# LPCB280_-_DRIVERS.net
KiCad netlist of a schematic drawn in Altium Designer
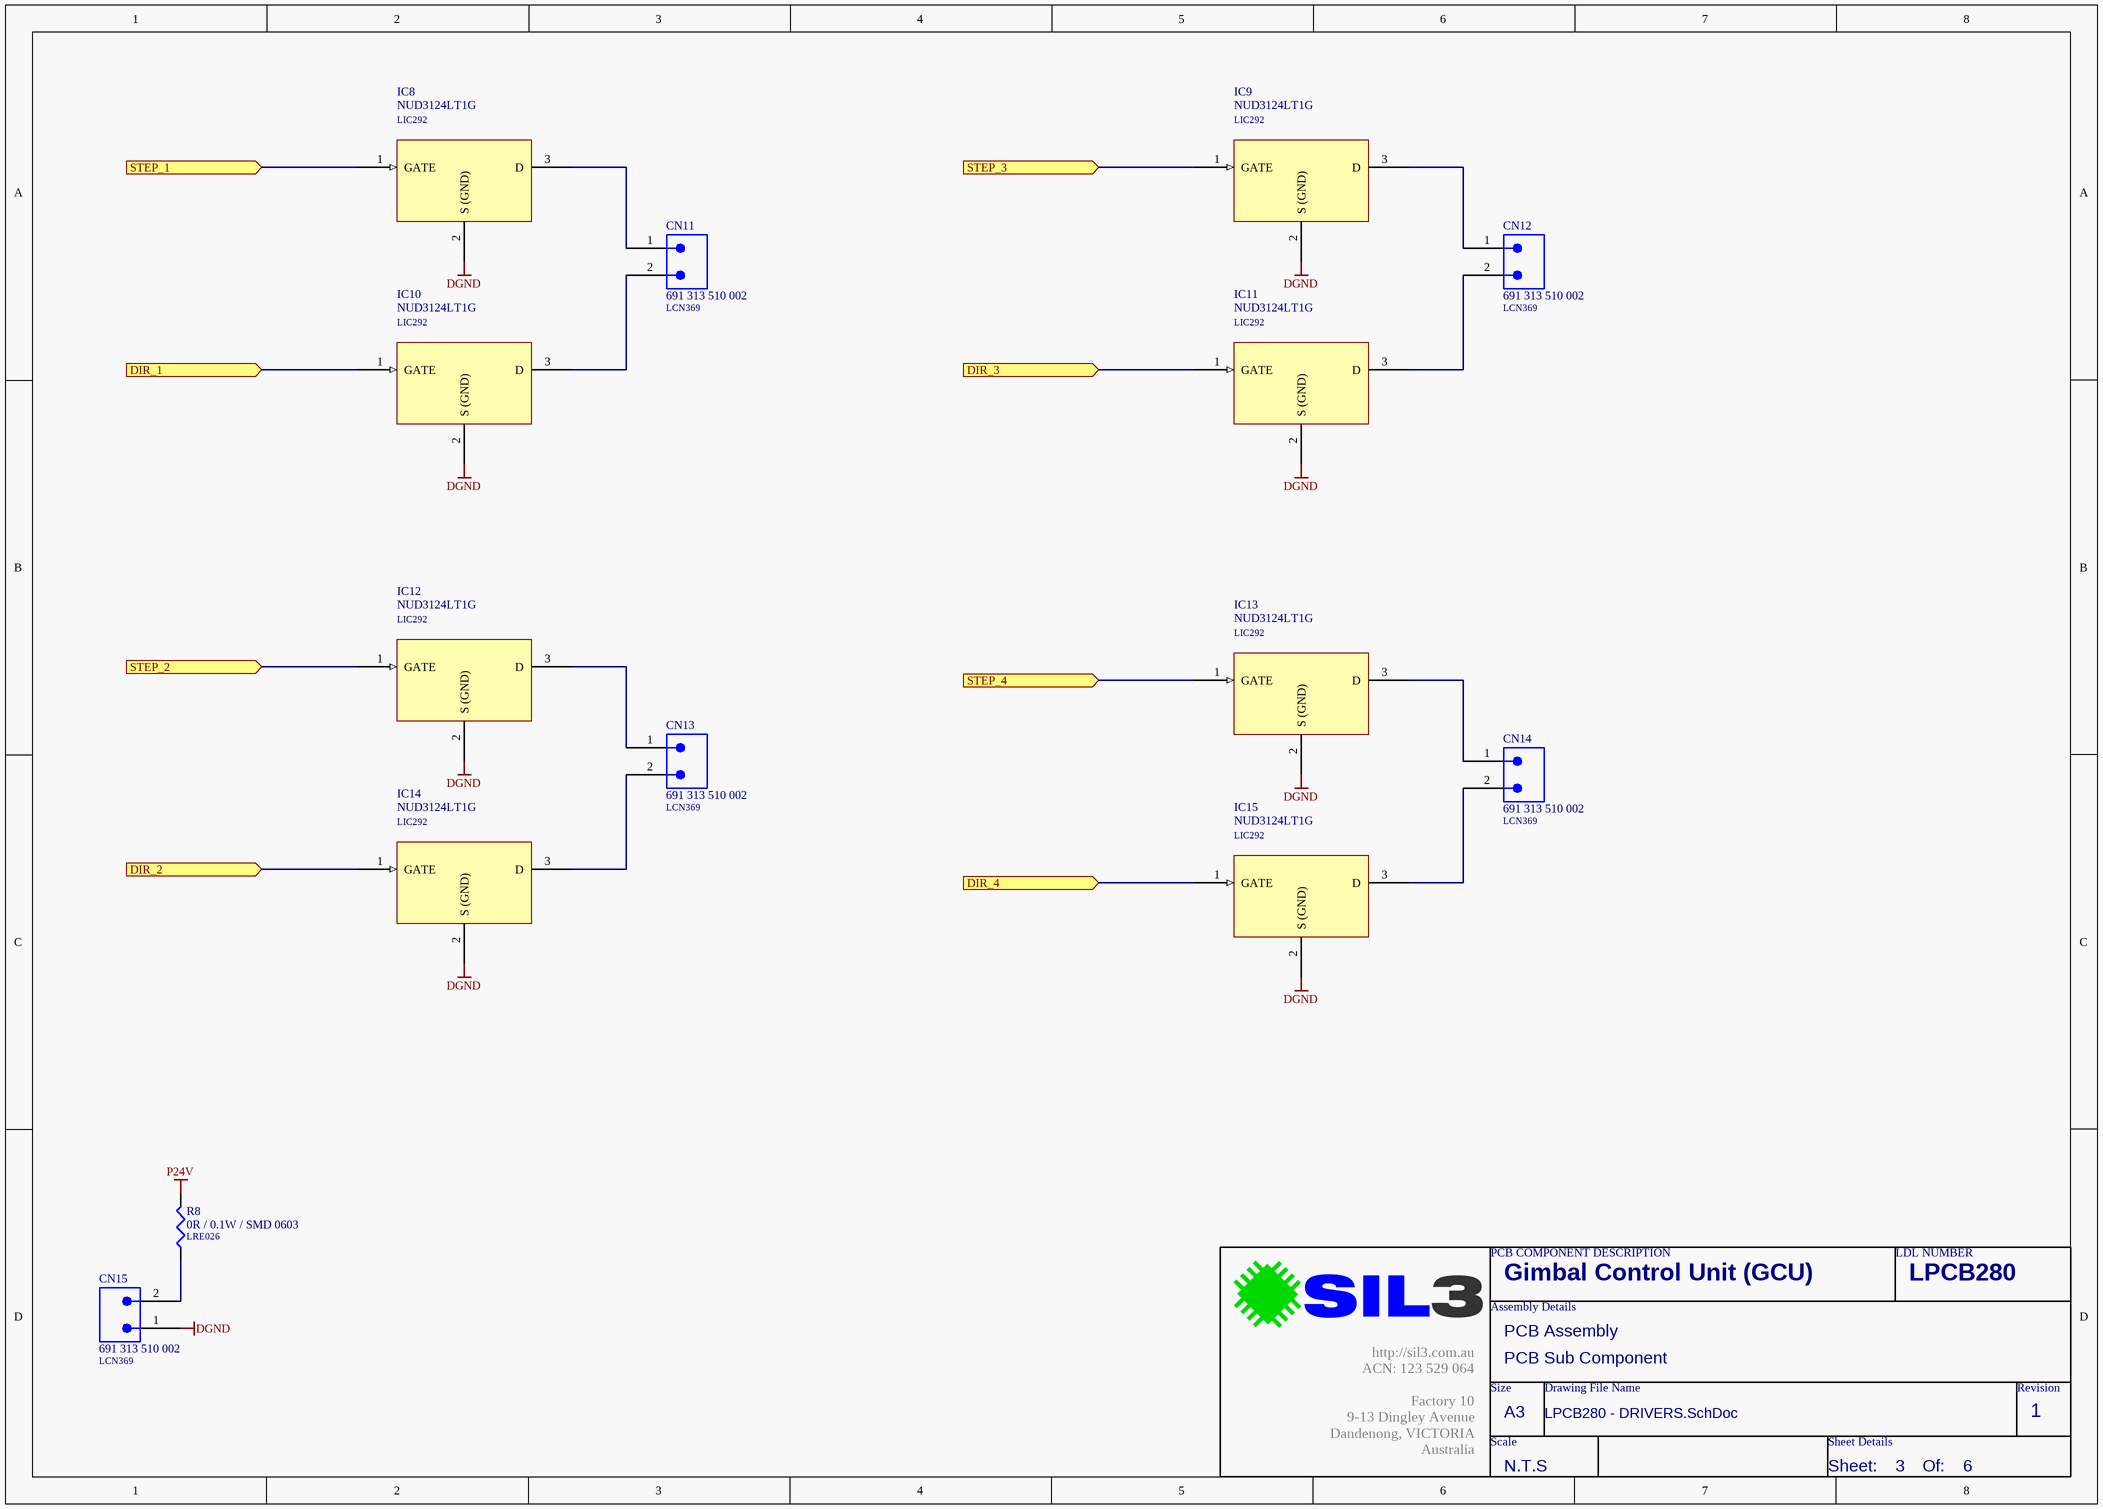
[diagram p0: LPCB280 - DRIVERS.SchDoc]

(export (version "E")
  (design (tool "Eeschema 10.0.6"))
  (components
    (comp (ref "CN11")
      (value "691 313 510 002")
      (footprint "691 313 510 002")
      (description "Connector, Pluggable Terminal Block, 5.08mm, 2 Way, PTH")
      (fields (field (name "LDL_NUMBER") "LCN369"))
      (libsource (lib "LDL_Connectors") (part "691 313 510 002"))
    )
    (comp (ref "CN12")
      (value "691 313 510 002")
      (footprint "691 313 510 002")
      (description "Connector, Pluggable Terminal Block, 5.08mm, 2 Way, PTH")
      (fields (field (name "LDL_NUMBER") "LCN369"))
      (libsource (lib "LDL_Connectors") (part "691 313 510 002"))
    )
    (comp (ref "CN13")
      (value "691 313 510 002")
      (footprint "691 313 510 002")
      (description "Connector, Pluggable Terminal Block, 5.08mm, 2 Way, PTH")
      (fields (field (name "LDL_NUMBER") "LCN369"))
      (libsource (lib "LDL_Connectors") (part "691 313 510 002"))
    )
    (comp (ref "CN14")
      (value "691 313 510 002")
      (footprint "691 313 510 002")
      (description "Connector, Pluggable Terminal Block, 5.08mm, 2 Way, PTH")
      (fields (field (name "LDL_NUMBER") "LCN369"))
      (libsource (lib "LDL_Connectors") (part "691 313 510 002"))
    )
    (comp (ref "CN15")
      (value "691 313 510 002")
      (footprint "691 313 510 002")
      (description "Connector, Pluggable Terminal Block, 5.08mm, 2 Way, PTH")
      (fields (field (name "LDL_NUMBER") "LCN369"))
      (libsource (lib "LDL_Connectors") (part "691 313 510 002"))
    )
    (comp (ref "IC8")
      (value "NUD3124LT1G")
      (footprint "LFP021__SOT23")
      (description "IC, Relay Driver, 28V Industrial, SMD SOT23 [LIC292]")
      (fields (field (name "LDL_NUMBER") "LIC292"))
      (libsource (lib "LDL_Semiconductors") (part "NUD3124LT1G"))
    )
    (comp (ref "IC9")
      (value "NUD3124LT1G")
      (footprint "LFP021__SOT23")
      (description "IC, Relay Driver, 28V Industrial, SMD SOT23 [LIC292]")
      (fields (field (name "LDL_NUMBER") "LIC292"))
      (libsource (lib "LDL_Semiconductors") (part "NUD3124LT1G"))
    )
    (comp (ref "IC10")
      (value "NUD3124LT1G")
      (footprint "LFP021__SOT23")
      (description "IC, Relay Driver, 28V Industrial, SMD SOT23 [LIC292]")
      (fields (field (name "LDL_NUMBER") "LIC292"))
      (libsource (lib "LDL_Semiconductors") (part "NUD3124LT1G"))
    )
    (comp (ref "IC11")
      (value "NUD3124LT1G")
      (footprint "LFP021__SOT23")
      (description "IC, Relay Driver, 28V Industrial, SMD SOT23 [LIC292]")
      (fields (field (name "LDL_NUMBER") "LIC292"))
      (libsource (lib "LDL_Semiconductors") (part "NUD3124LT1G"))
    )
    (comp (ref "IC12")
      (value "NUD3124LT1G")
      (footprint "LFP021__SOT23")
      (description "IC, Relay Driver, 28V Industrial, SMD SOT23 [LIC292]")
      (fields (field (name "LDL_NUMBER") "LIC292"))
      (libsource (lib "LDL_Semiconductors") (part "NUD3124LT1G"))
    )
    (comp (ref "IC13")
      (value "NUD3124LT1G")
      (footprint "LFP021__SOT23")
      (description "IC, Relay Driver, 28V Industrial, SMD SOT23 [LIC292]")
      (fields (field (name "LDL_NUMBER") "LIC292"))
      (libsource (lib "LDL_Semiconductors") (part "NUD3124LT1G"))
    )
    (comp (ref "IC14")
      (value "NUD3124LT1G")
      (footprint "LFP021__SOT23")
      (description "IC, Relay Driver, 28V Industrial, SMD SOT23 [LIC292]")
      (fields (field (name "LDL_NUMBER") "LIC292"))
      (libsource (lib "LDL_Semiconductors") (part "NUD3124LT1G"))
    )
    (comp (ref "IC15")
      (value "NUD3124LT1G")
      (footprint "LFP021__SOT23")
      (description "IC, Relay Driver, 28V Industrial, SMD SOT23 [LIC292]")
      (fields (field (name "LDL_NUMBER") "LIC292"))
      (libsource (lib "LDL_Semiconductors") (part "NUD3124LT1G"))
    )
    (comp (ref "R8")
      (value "0R / 0.1W / SMD 0603")
      (footprint "LFP020__CR1608-0603-IPC7351_B")
      (description "Resistor, Ceramic Chip, 0R, 0.1W, SMD 0603 [LRE026]")
      (fields (field (name "LDL_NUMBER") "LRE026"))
      (libsource (lib "LDL_Resistors") (part "0R / 0.1W / SMD 0603"))
    )
  )
  (nets
    (net (code "1") (name "/DIR_1") (class "Default")
      (node (ref "IC10") (pin "1") (pinfunction "GATE_1") (pintype "input"))
    )
    (net (code "2") (name "/DIR_2") (class "Default")
      (node (ref "IC14") (pin "1") (pinfunction "GATE_1") (pintype "input"))
    )
    (net (code "3") (name "/DIR_3") (class "Default")
      (node (ref "IC11") (pin "1") (pinfunction "GATE_1") (pintype "input"))
    )
    (net (code "4") (name "/DIR_4") (class "Default")
      (node (ref "IC15") (pin "1") (pinfunction "GATE_1") (pintype "input"))
    )
    (net (code "5") (name "/STEP_1") (class "Default")
      (node (ref "IC8") (pin "1") (pinfunction "GATE_1") (pintype "input"))
    )
    (net (code "6") (name "/STEP_2") (class "Default")
      (node (ref "IC12") (pin "1") (pinfunction "GATE_1") (pintype "input"))
    )
    (net (code "7") (name "/STEP_3") (class "Default")
      (node (ref "IC9") (pin "1") (pinfunction "GATE_1") (pintype "input"))
    )
    (net (code "8") (name "/STEP_4") (class "Default")
      (node (ref "IC13") (pin "1") (pinfunction "GATE_1") (pintype "input"))
    )
    (net (code "9") (name "DGND") (class "Default")
      (node (ref "CN15") (pin "1") (pinfunction "1_1") (pintype "passive"))
      (node (ref "IC10") (pin "2") (pinfunction "S_(GND)_2") (pintype "passive"))
      (node (ref "IC11") (pin "2") (pinfunction "S_(GND)_2") (pintype "passive"))
      (node (ref "IC12") (pin "2") (pinfunction "S_(GND)_2") (pintype "passive"))
      (node (ref "IC13") (pin "2") (pinfunction "S_(GND)_2") (pintype "passive"))
      (node (ref "IC14") (pin "2") (pinfunction "S_(GND)_2") (pintype "passive"))
      (node (ref "IC15") (pin "2") (pinfunction "S_(GND)_2") (pintype "passive"))
      (node (ref "IC8") (pin "2") (pinfunction "S_(GND)_2") (pintype "passive"))
      (node (ref "IC9") (pin "2") (pinfunction "S_(GND)_2") (pintype "passive"))
    )
    (net (code "10") (name "Net-(CN15-Pad2)") (class "Default")
      (node (ref "CN15") (pin "2") (pinfunction "2_2") (pintype "passive"))
      (node (ref "R8") (pin "1") (pintype "passive"))
    )
    (net (code "11") (name "Net-(IC8-D)") (class "Default")
      (node (ref "CN11") (pin "1") (pinfunction "1_1") (pintype "passive"))
      (node (ref "IC8") (pin "3") (pinfunction "D_3") (pintype "passive"))
    )
    (net (code "12") (name "Net-(IC9-D)") (class "Default")
      (node (ref "CN12") (pin "1") (pinfunction "1_1") (pintype "passive"))
      (node (ref "IC9") (pin "3") (pinfunction "D_3") (pintype "passive"))
    )
    (net (code "13") (name "Net-(IC10-D)") (class "Default")
      (node (ref "CN11") (pin "2") (pinfunction "2_2") (pintype "passive"))
      (node (ref "IC10") (pin "3") (pinfunction "D_3") (pintype "passive"))
    )
    (net (code "14") (name "Net-(IC11-D)") (class "Default")
      (node (ref "CN12") (pin "2") (pinfunction "2_2") (pintype "passive"))
      (node (ref "IC11") (pin "3") (pinfunction "D_3") (pintype "passive"))
    )
    (net (code "15") (name "Net-(IC12-D)") (class "Default")
      (node (ref "CN13") (pin "1") (pinfunction "1_1") (pintype "passive"))
      (node (ref "IC12") (pin "3") (pinfunction "D_3") (pintype "passive"))
    )
    (net (code "16") (name "Net-(IC13-D)") (class "Default")
      (node (ref "CN14") (pin "1") (pinfunction "1_1") (pintype "passive"))
      (node (ref "IC13") (pin "3") (pinfunction "D_3") (pintype "passive"))
    )
    (net (code "17") (name "Net-(IC14-D)") (class "Default")
      (node (ref "CN13") (pin "2") (pinfunction "2_2") (pintype "passive"))
      (node (ref "IC14") (pin "3") (pinfunction "D_3") (pintype "passive"))
    )
    (net (code "18") (name "Net-(IC15-D)") (class "Default")
      (node (ref "CN14") (pin "2") (pinfunction "2_2") (pintype "passive"))
      (node (ref "IC15") (pin "3") (pinfunction "D_3") (pintype "passive"))
    )
    (net (code "19") (name "P24V") (class "Default") (node (ref "R8") (pin "2") (pintype "passive")))
  )
)
